# SERVOS.net
KiCad netlist of a schematic drawn in Altium Designer
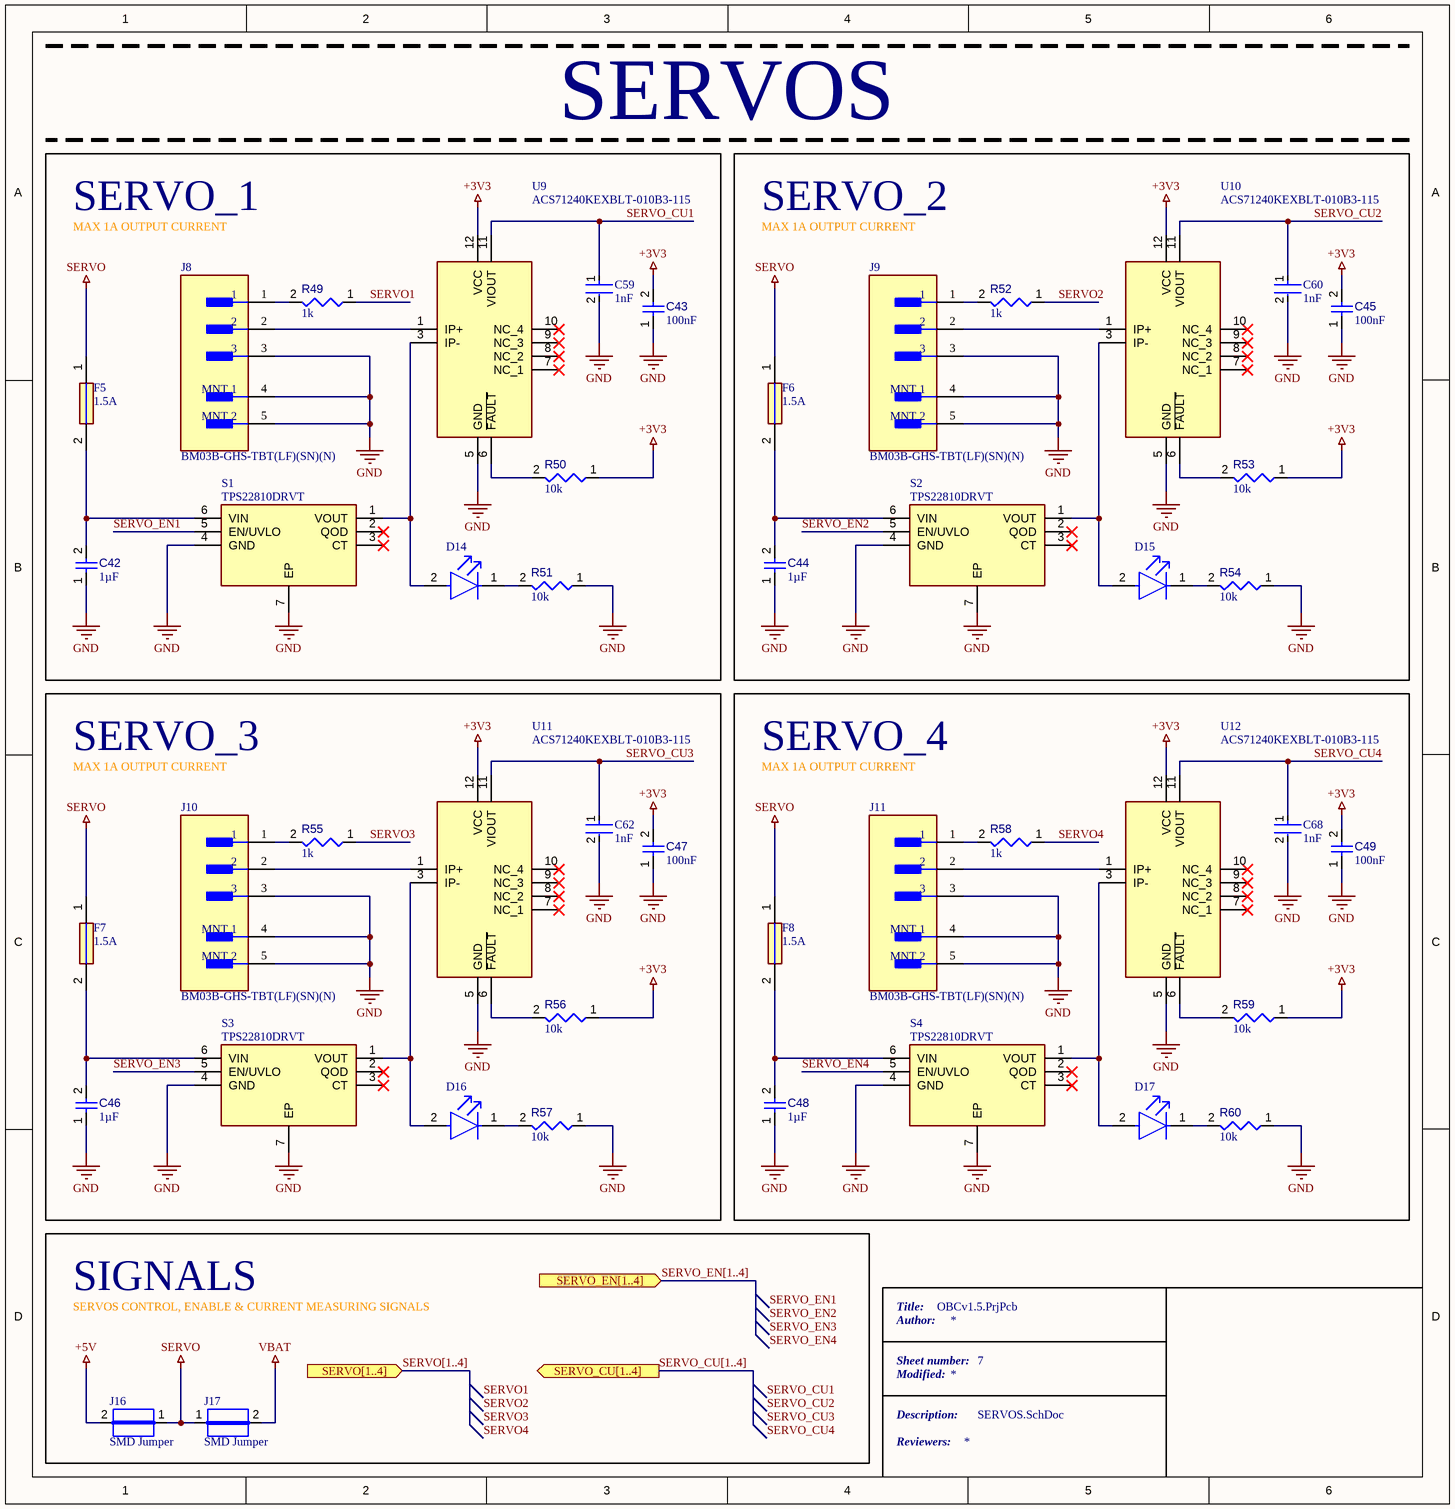
[diagram p0: SERVOS.SchDoc]

(export (version "E")
  (design (tool "Eeschema 10.0.6"))
  (components
    (comp (ref "C42")
      (value "1µF")
      (footprint "CAPC0402(1005)60_L")
      (description "Chip Capacitor, 1µF +/-20%, 10V, 0402, Thickness 0.6 mm")
      (fields (field (name "TOLERANCE") "10%") (field (name "Comment") "Capacitor 1µF +/-20% 10V 0402"))
      (libsource (lib "PWr in Space team") (part "CAP-NP-2"))
    )
    (comp (ref "C43")
      (value "100nF")
      (footprint "CAPC0402(1005)60_L")
      (description "Chip Capacitor, 100nF +/-20%, 10V, 0402, Thickness 0.6 mm")
      (fields (field (name "TOLERANCE") "20%") (field (name "Comment") "Capacitor 100nF +/-20% 10V 0402"))
      (libsource (lib "PWr in Space team") (part "CAP-NP-2"))
    )
    (comp (ref "C44")
      (value "1µF")
      (footprint "CAPC0402(1005)60_L")
      (description "Chip Capacitor, 1µF +/-20%, 10V, 0402, Thickness 0.6 mm")
      (fields (field (name "TOLERANCE") "10%") (field (name "Comment") "Capacitor 1µF +/-20% 10V 0402"))
      (libsource (lib "PWr in Space team") (part "CAP-NP-2"))
    )
    (comp (ref "C45")
      (value "100nF")
      (footprint "CAPC0402(1005)60_L")
      (description "Chip Capacitor, 100nF +/-20%, 10V, 0402, Thickness 0.6 mm")
      (fields (field (name "TOLERANCE") "20%") (field (name "Comment") "Capacitor 100nF +/-20% 10V 0402"))
      (libsource (lib "PWr in Space team") (part "CAP-NP-2"))
    )
    (comp (ref "C46")
      (value "1µF")
      (footprint "CAPC0402(1005)60_L")
      (description "Chip Capacitor, 1µF +/-20%, 10V, 0402, Thickness 0.6 mm")
      (fields (field (name "TOLERANCE") "10%") (field (name "Comment") "Capacitor 1µF +/-20% 10V 0402"))
      (libsource (lib "PWr in Space team") (part "CAP-NP-2"))
    )
    (comp (ref "C47")
      (value "100nF")
      (footprint "CAPC0402(1005)60_L")
      (description "Chip Capacitor, 100nF +/-20%, 10V, 0402, Thickness 0.6 mm")
      (fields (field (name "TOLERANCE") "20%") (field (name "Comment") "Capacitor 100nF +/-20% 10V 0402"))
      (libsource (lib "PWr in Space team") (part "CAP-NP-2"))
    )
    (comp (ref "C48")
      (value "1µF")
      (footprint "CAPC0402(1005)60_L")
      (description "Chip Capacitor, 1µF +/-20%, 10V, 0402, Thickness 0.6 mm")
      (fields (field (name "TOLERANCE") "10%") (field (name "Comment") "Capacitor 1µF +/-20% 10V 0402"))
      (libsource (lib "PWr in Space team") (part "CAP-NP-2"))
    )
    (comp (ref "C49")
      (value "100nF")
      (footprint "CAPC0402(1005)60_L")
      (description "Chip Capacitor, 100nF +/-20%, 10V, 0402, Thickness 0.6 mm")
      (fields (field (name "TOLERANCE") "20%") (field (name "Comment") "Capacitor 100nF +/-20% 10V 0402"))
      (libsource (lib "PWr in Space team") (part "CAP-NP-2"))
    )
    (comp (ref "C59")
      (value "1nF")
      (footprint "FP-GRM155-0_05-IPC_B")
      (description "Chip Multilayer Ceramic Capacitors for General Purpose, 0402, 1000pF, C0G, 30ppm/°C, 5%, 50V")
      (fields (field (name "TOLERANCE") "5%") (field (name "VOLTAGE") "50V"))
      (libsource (lib "Altium Content Vault") (part "02cd4be3c70576c341d710602a673aa"))
    )
    (comp (ref "C60")
      (value "1nF")
      (footprint "FP-GRM155-0_05-IPC_B")
      (description "Chip Multilayer Ceramic Capacitors for General Purpose, 0402, 1000pF, C0G, 30ppm/°C, 5%, 50V")
      (fields (field (name "TOLERANCE") "5%") (field (name "VOLTAGE") "50V"))
      (libsource (lib "Altium Content Vault") (part "02cd4be3c70576c341d710602a673aa"))
    )
    (comp (ref "C62")
      (value "1nF")
      (footprint "FP-GRM155-0_05-IPC_B")
      (description "Chip Multilayer Ceramic Capacitors for General Purpose, 0402, 1000pF, C0G, 30ppm/°C, 5%, 50V")
      (fields (field (name "TOLERANCE") "5%") (field (name "VOLTAGE") "50V"))
      (libsource (lib "Altium Content Vault") (part "02cd4be3c70576c341d710602a673aa"))
    )
    (comp (ref "C68")
      (value "1nF")
      (footprint "FP-GRM155-0_05-IPC_B")
      (description "Chip Multilayer Ceramic Capacitors for General Purpose, 0402, 1000pF, C0G, 30ppm/°C, 5%, 50V")
      (fields (field (name "TOLERANCE") "5%") (field (name "VOLTAGE") "50V"))
      (libsource (lib "Altium Content Vault") (part "02cd4be3c70576c341d710602a673aa"))
    )
    (comp (ref "D14")
      (value "~")
      (footprint "FP-LTST-C191TBKT-MFG")
      (description "LED BLUE CLEAR CHIP SMD")
      (libsource (lib "Altium Content Vault") (part "8706943c75ba83719d021d2fdc84c58"))
    )
    (comp (ref "D15")
      (value "~")
      (footprint "FP-LTST-C191TBKT-MFG")
      (description "LED BLUE CLEAR CHIP SMD")
      (libsource (lib "Altium Content Vault") (part "8706943c75ba83719d021d2fdc84c58"))
    )
    (comp (ref "D16")
      (value "~")
      (footprint "FP-LTST-C191TBKT-MFG")
      (description "LED BLUE CLEAR CHIP SMD")
      (libsource (lib "Altium Content Vault") (part "8706943c75ba83719d021d2fdc84c58"))
    )
    (comp (ref "D17")
      (value "~")
      (footprint "FP-LTST-C191TBKT-MFG")
      (description "LED BLUE CLEAR CHIP SMD")
      (libsource (lib "Altium Content Vault") (part "8706943c75ba83719d021d2fdc84c58"))
    )
    (comp (ref "F5")
      (value "1.5A")
      (footprint "SamacSys:FUSC2516X100N")
      (description "Fuse")
      (fields (field (name "MANUFACTURER_PART_NUMBER") "PTSLR08058V300"))
      (libsource (lib "*") (part "PTSLR08058V300"))
    )
    (comp (ref "F6")
      (value "1.5A")
      (footprint "SamacSys:FUSC2516X100N")
      (description "Fuse")
      (fields (field (name "MANUFACTURER_PART_NUMBER") "PTSLR08058V300"))
      (libsource (lib "*") (part "PTSLR08058V300"))
    )
    (comp (ref "F7")
      (value "1.5A")
      (footprint "SamacSys:FUSC2516X100N")
      (description "Fuse")
      (fields (field (name "MANUFACTURER_PART_NUMBER") "PTSLR08058V300"))
      (libsource (lib "*") (part "PTSLR08058V300"))
    )
    (comp (ref "F8")
      (value "1.5A")
      (footprint "SamacSys:FUSC2516X100N")
      (description "Fuse")
      (fields (field (name "MANUFACTURER_PART_NUMBER") "PTSLR08058V300"))
      (libsource (lib "*") (part "PTSLR08058V300"))
    )
    (comp (ref "J8")
      (value "BM03B-GHS-TBT(LF)(SN)(N)")
      (footprint "FP-BM03B-GHS-TBT_LF_SN-MFG")
      (description "CONN HEADER SMD 3POS 1.25MM")
      (libsource (lib "Altium Content Vault") (part "38689d6f3df0f9b234c6ddcef280d85"))
    )
    (comp (ref "J9")
      (value "BM03B-GHS-TBT(LF)(SN)(N)")
      (footprint "FP-BM03B-GHS-TBT_LF_SN-MFG")
      (description "CONN HEADER SMD 3POS 1.25MM")
      (libsource (lib "Altium Content Vault") (part "38689d6f3df0f9b234c6ddcef280d85"))
    )
    (comp (ref "J10")
      (value "BM03B-GHS-TBT(LF)(SN)(N)")
      (footprint "FP-BM03B-GHS-TBT_LF_SN-MFG")
      (description "CONN HEADER SMD 3POS 1.25MM")
      (libsource (lib "Altium Content Vault") (part "38689d6f3df0f9b234c6ddcef280d85"))
    )
    (comp (ref "J11")
      (value "BM03B-GHS-TBT(LF)(SN)(N)")
      (footprint "FP-BM03B-GHS-TBT_LF_SN-MFG")
      (description "CONN HEADER SMD 3POS 1.25MM")
      (libsource (lib "Altium Content Vault") (part "38689d6f3df0f9b234c6ddcef280d85"))
    )
    (comp (ref "J16")
      (value "SMD Jumper")
      (footprint "RESC3225X06N")
      (description "SMD Jumper, size 1210 (imperial)")
      (libsource (lib "PWr in Space team") (part "JUMPER"))
    )
    (comp (ref "J17")
      (value "SMD Jumper")
      (footprint "RESC3225X06N")
      (description "SMD Jumper, size 1210 (imperial)")
      (libsource (lib "") (part "JUMPER_1"))
    )
    (comp (ref "R49")
      (value "1k")
      (footprint "RESC0402(1005)_L")
      (description "Chip Resistor, 1 kOhms, +/-5 %, 63 mW, -55 to 155 degC, 0402")
      (fields (field (name "TOLERANCE") "5%") (field (name "POWER") "63mW"))
      (libsource (lib "PWr in Space team") (part "RES-2"))
    )
    (comp (ref "R50")
      (value "10k")
      (footprint "RESC0402(1005)_L")
      (description "Chip Resistor, 10 kOhms, +/-1 %, 63 mW, -55 to 125 degC, 0402")
      (fields (field (name "POWER") "63mW") (field (name "TOLERANCE") "1%"))
      (libsource (lib "PWr in Space team") (part "RES-2"))
    )
    (comp (ref "R51")
      (value "10k")
      (footprint "RESC0402(1005)_L")
      (description "Chip Resistor, 10 kOhms, +/-1 %, 63 mW, -55 to 125 degC, 0402")
      (fields (field (name "POWER") "63mW") (field (name "TOLERANCE") "1%"))
      (libsource (lib "PWr in Space team") (part "RES-2"))
    )
    (comp (ref "R52")
      (value "1k")
      (footprint "RESC0402(1005)_L")
      (description "Chip Resistor, 1 kOhms, +/-5 %, 63 mW, -55 to 155 degC, 0402")
      (fields (field (name "TOLERANCE") "5%") (field (name "POWER") "63mW"))
      (libsource (lib "PWr in Space team") (part "RES-2"))
    )
    (comp (ref "R53")
      (value "10k")
      (footprint "RESC0402(1005)_L")
      (description "Chip Resistor, 10 kOhms, +/-1 %, 63 mW, -55 to 125 degC, 0402")
      (fields (field (name "POWER") "63mW") (field (name "TOLERANCE") "1%"))
      (libsource (lib "PWr in Space team") (part "RES-2"))
    )
    (comp (ref "R54")
      (value "10k")
      (footprint "RESC0402(1005)_L")
      (description "Chip Resistor, 10 kOhms, +/-1 %, 63 mW, -55 to 125 degC, 0402")
      (fields (field (name "POWER") "63mW") (field (name "TOLERANCE") "1%"))
      (libsource (lib "PWr in Space team") (part "RES-2"))
    )
    (comp (ref "R55")
      (value "1k")
      (footprint "RESC0402(1005)_L")
      (description "Chip Resistor, 1 kOhms, +/-5 %, 63 mW, -55 to 155 degC, 0402")
      (fields (field (name "TOLERANCE") "5%") (field (name "POWER") "63mW"))
      (libsource (lib "PWr in Space team") (part "RES-2"))
    )
    (comp (ref "R56")
      (value "10k")
      (footprint "RESC0402(1005)_L")
      (description "Chip Resistor, 10 kOhms, +/-1 %, 63 mW, -55 to 125 degC, 0402")
      (fields (field (name "POWER") "63mW") (field (name "TOLERANCE") "1%"))
      (libsource (lib "PWr in Space team") (part "RES-2"))
    )
    (comp (ref "R57")
      (value "10k")
      (footprint "RESC0402(1005)_L")
      (description "Chip Resistor, 10 kOhms, +/-1 %, 63 mW, -55 to 125 degC, 0402")
      (fields (field (name "POWER") "63mW") (field (name "TOLERANCE") "1%"))
      (libsource (lib "PWr in Space team") (part "RES-2"))
    )
    (comp (ref "R58")
      (value "1k")
      (footprint "RESC0402(1005)_L")
      (description "Chip Resistor, 1 kOhms, +/-5 %, 63 mW, -55 to 155 degC, 0402")
      (fields (field (name "TOLERANCE") "5%") (field (name "POWER") "63mW"))
      (libsource (lib "PWr in Space team") (part "RES-2"))
    )
    (comp (ref "R59")
      (value "10k")
      (footprint "RESC0402(1005)_L")
      (description "Chip Resistor, 10 kOhms, +/-1 %, 63 mW, -55 to 125 degC, 0402")
      (fields (field (name "POWER") "63mW") (field (name "TOLERANCE") "1%"))
      (libsource (lib "PWr in Space team") (part "RES-2"))
    )
    (comp (ref "R60")
      (value "10k")
      (footprint "RESC0402(1005)_L")
      (description "Chip Resistor, 10 kOhms, +/-1 %, 63 mW, -55 to 125 degC, 0402")
      (fields (field (name "POWER") "63mW") (field (name "TOLERANCE") "1%"))
      (libsource (lib "PWr in Space team") (part "RES-2"))
    )
    (comp (ref "S1")
      (value "TPS22810DRVT")
      (footprint "SamacSys:SON65P200X200X80-7N")
      (description "Switch")
      (fields (field (name "MOUSER PART NUMBER") "595-TPS22810DRVT"))
      (libsource (lib "*") (part "TPS22810DRVT"))
    )
    (comp (ref "S2")
      (value "TPS22810DRVT")
      (footprint "SamacSys:SON65P200X200X80-7N")
      (description "Switch")
      (fields (field (name "MOUSER PART NUMBER") "595-TPS22810DRVT"))
      (libsource (lib "*") (part "TPS22810DRVT"))
    )
    (comp (ref "S3")
      (value "TPS22810DRVT")
      (footprint "SamacSys:SON65P200X200X80-7N")
      (description "Switch")
      (fields (field (name "MOUSER PART NUMBER") "595-TPS22810DRVT"))
      (libsource (lib "*") (part "TPS22810DRVT"))
    )
    (comp (ref "S4")
      (value "TPS22810DRVT")
      (footprint "SamacSys:SON65P200X200X80-7N")
      (description "Switch")
      (fields (field (name "MOUSER PART NUMBER") "595-TPS22810DRVT"))
      (libsource (lib "*") (part "TPS22810DRVT"))
    )
    (comp (ref "U9")
      (value "ACS71240KEXBLT-010B3-115")
      (footprint "SamacSys:ACS71240KEXBLT010B3115")
      (description "Integrated Circuit")
      (fields (field (name "MOUSER PART NUMBER") "250-71240KEXBL0B3115"))
      (libsource (lib "*") (part "ACS71240KEXBLT-010B3-115"))
    )
    (comp (ref "U10")
      (value "ACS71240KEXBLT-010B3-115")
      (footprint "SamacSys:ACS71240KEXBLT010B3115")
      (description "Integrated Circuit")
      (fields (field (name "MOUSER PART NUMBER") "250-71240KEXBL0B3115"))
      (libsource (lib "*") (part "ACS71240KEXBLT-010B3-115"))
    )
    (comp (ref "U11")
      (value "ACS71240KEXBLT-010B3-115")
      (footprint "SamacSys:ACS71240KEXBLT010B3115")
      (description "Integrated Circuit")
      (fields (field (name "MOUSER PART NUMBER") "250-71240KEXBL0B3115"))
      (libsource (lib "*") (part "ACS71240KEXBLT-010B3-115"))
    )
    (comp (ref "U12")
      (value "ACS71240KEXBLT-010B3-115")
      (footprint "SamacSys:ACS71240KEXBLT010B3115")
      (description "Integrated Circuit")
      (fields (field (name "MOUSER PART NUMBER") "250-71240KEXBL0B3115"))
      (libsource (lib "*") (part "ACS71240KEXBLT-010B3-115"))
    )
  )
  (nets
    (net (code "1") (name "+3V3") (class "Default")
      (node (ref "C43") (pin "2") (pinfunction "2_2") (pintype "passive"))
      (node (ref "C45") (pin "2") (pinfunction "2_2") (pintype "passive"))
      (node (ref "C47") (pin "2") (pinfunction "2_2") (pintype "passive"))
      (node (ref "C49") (pin "2") (pinfunction "2_2") (pintype "passive"))
      (node (ref "R50") (pin "1") (pinfunction "1_1") (pintype "passive"))
      (node (ref "R53") (pin "1") (pinfunction "1_1") (pintype "passive"))
      (node (ref "R56") (pin "1") (pinfunction "1_1") (pintype "passive"))
      (node (ref "R59") (pin "1") (pinfunction "1_1") (pintype "passive"))
      (node (ref "U10") (pin "12") (pinfunction "VCC_12") (pintype "passive"))
      (node (ref "U11") (pin "12") (pinfunction "VCC_12") (pintype "passive"))
      (node (ref "U12") (pin "12") (pinfunction "VCC_12") (pintype "passive"))
      (node (ref "U9") (pin "12") (pinfunction "VCC_12") (pintype "passive"))
    )
    (net (code "2") (name "+5V") (class "Default")
      (node (ref "J16") (pin "2") (pinfunction "2_2") (pintype "passive"))
    )
    (net (code "3") (name "/SERVO1") (class "Default")
      (node (ref "R49") (pin "1") (pinfunction "1_1") (pintype "passive"))
    )
    (net (code "4") (name "/SERVO2") (class "Default")
      (node (ref "R52") (pin "1") (pinfunction "1_1") (pintype "passive"))
    )
    (net (code "5") (name "/SERVO3") (class "Default")
      (node (ref "R55") (pin "1") (pinfunction "1_1") (pintype "passive"))
    )
    (net (code "6") (name "/SERVO4") (class "Default")
      (node (ref "R58") (pin "1") (pinfunction "1_1") (pintype "passive"))
    )
    (net (code "8") (name "/SERVO_CU1") (class "Default")
      (node (ref "C59") (pin "1") (pinfunction "1_1") (pintype "passive"))
      (node (ref "U9") (pin "11") (pinfunction "VIOUT_11") (pintype "passive"))
    )
    (net (code "9") (name "/SERVO_CU2") (class "Default")
      (node (ref "C60") (pin "1") (pinfunction "1_1") (pintype "passive"))
      (node (ref "U10") (pin "11") (pinfunction "VIOUT_11") (pintype "passive"))
    )
    (net (code "10") (name "/SERVO_CU3") (class "Default")
      (node (ref "C62") (pin "1") (pinfunction "1_1") (pintype "passive"))
      (node (ref "U11") (pin "11") (pinfunction "VIOUT_11") (pintype "passive"))
    )
    (net (code "11") (name "/SERVO_CU4") (class "Default")
      (node (ref "C68") (pin "1") (pinfunction "1_1") (pintype "passive"))
      (node (ref "U12") (pin "11") (pinfunction "VIOUT_11") (pintype "passive"))
    )
    (net (code "13") (name "/SERVO_EN1") (class "Default")
      (node (ref "S1") (pin "5") (pinfunction "EN/UVLO_5") (pintype "passive"))
    )
    (net (code "14") (name "/SERVO_EN2") (class "Default")
      (node (ref "S2") (pin "5") (pinfunction "EN/UVLO_5") (pintype "passive"))
    )
    (net (code "15") (name "/SERVO_EN3") (class "Default")
      (node (ref "S3") (pin "5") (pinfunction "EN/UVLO_5") (pintype "passive"))
    )
    (net (code "16") (name "/SERVO_EN4") (class "Default")
      (node (ref "S4") (pin "5") (pinfunction "EN/UVLO_5") (pintype "passive"))
    )
    (net (code "18") (name "GND") (class "Default")
      (node (ref "C42") (pin "1") (pinfunction "1_1") (pintype "passive"))
      (node (ref "C43") (pin "1") (pinfunction "1_1") (pintype "passive"))
      (node (ref "C44") (pin "1") (pinfunction "1_1") (pintype "passive"))
      (node (ref "C45") (pin "1") (pinfunction "1_1") (pintype "passive"))
      (node (ref "C46") (pin "1") (pinfunction "1_1") (pintype "passive"))
      (node (ref "C47") (pin "1") (pinfunction "1_1") (pintype "passive"))
      (node (ref "C48") (pin "1") (pinfunction "1_1") (pintype "passive"))
      (node (ref "C49") (pin "1") (pinfunction "1_1") (pintype "passive"))
      (node (ref "C59") (pin "2") (pinfunction "2_2") (pintype "passive"))
      (node (ref "C60") (pin "2") (pinfunction "2_2") (pintype "passive"))
      (node (ref "C62") (pin "2") (pinfunction "2_2") (pintype "passive"))
      (node (ref "C68") (pin "2") (pinfunction "2_2") (pintype "passive"))
      (node (ref "J10") (pin "3") (pinfunction "3_3") (pintype "passive"))
      (node (ref "J10") (pin "4") (pinfunction "MNT_1_4") (pintype "passive"))
      (node (ref "J10") (pin "5") (pinfunction "MNT_2_5") (pintype "passive"))
      (node (ref "J11") (pin "3") (pinfunction "3_3") (pintype "passive"))
      (node (ref "J11") (pin "4") (pinfunction "MNT_1_4") (pintype "passive"))
      (node (ref "J11") (pin "5") (pinfunction "MNT_2_5") (pintype "passive"))
      (node (ref "J8") (pin "3") (pinfunction "3_3") (pintype "passive"))
      (node (ref "J8") (pin "4") (pinfunction "MNT_1_4") (pintype "passive"))
      (node (ref "J8") (pin "5") (pinfunction "MNT_2_5") (pintype "passive"))
      (node (ref "J9") (pin "3") (pinfunction "3_3") (pintype "passive"))
      (node (ref "J9") (pin "4") (pinfunction "MNT_1_4") (pintype "passive"))
      (node (ref "J9") (pin "5") (pinfunction "MNT_2_5") (pintype "passive"))
      (node (ref "R51") (pin "1") (pinfunction "1_1") (pintype "passive"))
      (node (ref "R54") (pin "1") (pinfunction "1_1") (pintype "passive"))
      (node (ref "R57") (pin "1") (pinfunction "1_1") (pintype "passive"))
      (node (ref "R60") (pin "1") (pinfunction "1_1") (pintype "passive"))
      (node (ref "S1") (pin "4") (pinfunction "GND_4") (pintype "passive"))
      (node (ref "S1") (pin "7") (pinfunction "EP_7") (pintype "passive"))
      (node (ref "S2") (pin "4") (pinfunction "GND_4") (pintype "passive"))
      (node (ref "S2") (pin "7") (pinfunction "EP_7") (pintype "passive"))
      (node (ref "S3") (pin "4") (pinfunction "GND_4") (pintype "passive"))
      (node (ref "S3") (pin "7") (pinfunction "EP_7") (pintype "passive"))
      (node (ref "S4") (pin "4") (pinfunction "GND_4") (pintype "passive"))
      (node (ref "S4") (pin "7") (pinfunction "EP_7") (pintype "passive"))
      (node (ref "U10") (pin "5") (pinfunction "GND_5") (pintype "passive"))
      (node (ref "U11") (pin "5") (pinfunction "GND_5") (pintype "passive"))
      (node (ref "U12") (pin "5") (pinfunction "GND_5") (pintype "passive"))
      (node (ref "U9") (pin "5") (pinfunction "GND_5") (pintype "passive"))
    )
    (net (code "19") (name "Net-(D14-A)") (class "Default")
      (node (ref "D14") (pin "2") (pinfunction "A_2") (pintype "passive"))
      (node (ref "S1") (pin "1") (pinfunction "VOUT_1") (pintype "passive"))
      (node (ref "U9") (pin "3") (pinfunction "IP-_3") (pintype "passive"))
    )
    (net (code "20") (name "Net-(D14-C)") (class "Default")
      (node (ref "D14") (pin "1") (pinfunction "C_1") (pintype "passive"))
      (node (ref "R51") (pin "2") (pinfunction "2_2") (pintype "passive"))
    )
    (net (code "21") (name "Net-(D15-A)") (class "Default")
      (node (ref "D15") (pin "2") (pinfunction "A_2") (pintype "passive"))
      (node (ref "S2") (pin "1") (pinfunction "VOUT_1") (pintype "passive"))
      (node (ref "U10") (pin "3") (pinfunction "IP-_3") (pintype "passive"))
    )
    (net (code "22") (name "Net-(D15-C)") (class "Default")
      (node (ref "D15") (pin "1") (pinfunction "C_1") (pintype "passive"))
      (node (ref "R54") (pin "2") (pinfunction "2_2") (pintype "passive"))
    )
    (net (code "23") (name "Net-(D16-A)") (class "Default")
      (node (ref "D16") (pin "2") (pinfunction "A_2") (pintype "passive"))
      (node (ref "S3") (pin "1") (pinfunction "VOUT_1") (pintype "passive"))
      (node (ref "U11") (pin "3") (pinfunction "IP-_3") (pintype "passive"))
    )
    (net (code "24") (name "Net-(D16-C)") (class "Default")
      (node (ref "D16") (pin "1") (pinfunction "C_1") (pintype "passive"))
      (node (ref "R57") (pin "2") (pinfunction "2_2") (pintype "passive"))
    )
    (net (code "25") (name "Net-(D17-A)") (class "Default")
      (node (ref "D17") (pin "2") (pinfunction "A_2") (pintype "passive"))
      (node (ref "S4") (pin "1") (pinfunction "VOUT_1") (pintype "passive"))
      (node (ref "U12") (pin "3") (pinfunction "IP-_3") (pintype "passive"))
    )
    (net (code "26") (name "Net-(D17-C)") (class "Default")
      (node (ref "D17") (pin "1") (pinfunction "C_1") (pintype "passive"))
      (node (ref "R60") (pin "2") (pinfunction "2_2") (pintype "passive"))
    )
    (net (code "27") (name "Net-(J8-Pad1)") (class "Default")
      (node (ref "J8") (pin "1") (pinfunction "1_1") (pintype "passive"))
      (node (ref "R49") (pin "2") (pinfunction "2_2") (pintype "passive"))
    )
    (net (code "28") (name "Net-(J9-Pad1)") (class "Default")
      (node (ref "J9") (pin "1") (pinfunction "1_1") (pintype "passive"))
      (node (ref "R52") (pin "2") (pinfunction "2_2") (pintype "passive"))
    )
    (net (code "29") (name "Net-(J10-Pad1)") (class "Default")
      (node (ref "J10") (pin "1") (pinfunction "1_1") (pintype "passive"))
      (node (ref "R55") (pin "2") (pinfunction "2_2") (pintype "passive"))
    )
    (net (code "30") (name "Net-(J11-Pad1)") (class "Default")
      (node (ref "J11") (pin "1") (pinfunction "1_1") (pintype "passive"))
      (node (ref "R58") (pin "2") (pinfunction "2_2") (pintype "passive"))
    )
    (net (code "31") (name "Net-(S1-VIN)") (class "Default")
      (node (ref "C42") (pin "2") (pinfunction "2_2") (pintype "passive"))
      (node (ref "F5") (pin "2") (pinfunction "2_2") (pintype "passive"))
      (node (ref "S1") (pin "6") (pinfunction "VIN_6") (pintype "passive"))
    )
    (net (code "32") (name "Net-(S2-VIN)") (class "Default")
      (node (ref "C44") (pin "2") (pinfunction "2_2") (pintype "passive"))
      (node (ref "F6") (pin "2") (pinfunction "2_2") (pintype "passive"))
      (node (ref "S2") (pin "6") (pinfunction "VIN_6") (pintype "passive"))
    )
    (net (code "33") (name "Net-(S3-VIN)") (class "Default")
      (node (ref "C46") (pin "2") (pinfunction "2_2") (pintype "passive"))
      (node (ref "F7") (pin "2") (pinfunction "2_2") (pintype "passive"))
      (node (ref "S3") (pin "6") (pinfunction "VIN_6") (pintype "passive"))
    )
    (net (code "34") (name "Net-(S4-VIN)") (class "Default")
      (node (ref "C48") (pin "2") (pinfunction "2_2") (pintype "passive"))
      (node (ref "F8") (pin "2") (pinfunction "2_2") (pintype "passive"))
      (node (ref "S4") (pin "6") (pinfunction "VIN_6") (pintype "passive"))
    )
    (net (code "35") (name "Net-(U9-IP+)") (class "Default")
      (node (ref "J8") (pin "2") (pinfunction "2_2") (pintype "passive"))
      (node (ref "U9") (pin "1") (pinfunction "IP+_1") (pintype "passive"))
    )
    (net (code "36") (name "Net-(U9-~{FAULT})") (class "Default")
      (node (ref "R50") (pin "2") (pinfunction "2_2") (pintype "passive"))
      (node (ref "U9") (pin "6") (pinfunction "~{FAULT}_6") (pintype "passive"))
    )
    (net (code "37") (name "Net-(U10-IP+)") (class "Default")
      (node (ref "J9") (pin "2") (pinfunction "2_2") (pintype "passive"))
      (node (ref "U10") (pin "1") (pinfunction "IP+_1") (pintype "passive"))
    )
    (net (code "38") (name "Net-(U10-~{FAULT})") (class "Default")
      (node (ref "R53") (pin "2") (pinfunction "2_2") (pintype "passive"))
      (node (ref "U10") (pin "6") (pinfunction "~{FAULT}_6") (pintype "passive"))
    )
    (net (code "39") (name "Net-(U11-IP+)") (class "Default")
      (node (ref "J10") (pin "2") (pinfunction "2_2") (pintype "passive"))
      (node (ref "U11") (pin "1") (pinfunction "IP+_1") (pintype "passive"))
    )
    (net (code "40") (name "Net-(U11-~{FAULT})") (class "Default")
      (node (ref "R56") (pin "2") (pinfunction "2_2") (pintype "passive"))
      (node (ref "U11") (pin "6") (pinfunction "~{FAULT}_6") (pintype "passive"))
    )
    (net (code "41") (name "Net-(U12-IP+)") (class "Default")
      (node (ref "J11") (pin "2") (pinfunction "2_2") (pintype "passive"))
      (node (ref "U12") (pin "1") (pinfunction "IP+_1") (pintype "passive"))
    )
    (net (code "42") (name "Net-(U12-~{FAULT})") (class "Default")
      (node (ref "R59") (pin "2") (pinfunction "2_2") (pintype "passive"))
      (node (ref "U12") (pin "6") (pinfunction "~{FAULT}_6") (pintype "passive"))
    )
    (net (code "43") (name "SERVO") (class "Default")
      (node (ref "F5") (pin "1") (pinfunction "1_1") (pintype "passive"))
      (node (ref "F6") (pin "1") (pinfunction "1_1") (pintype "passive"))
      (node (ref "F7") (pin "1") (pinfunction "1_1") (pintype "passive"))
      (node (ref "F8") (pin "1") (pinfunction "1_1") (pintype "passive"))
      (node (ref "J16") (pin "1") (pinfunction "1_1") (pintype "passive"))
      (node (ref "J17") (pin "1") (pinfunction "1_1") (pintype "passive"))
    )
    (net (code "44") (name "VBAT") (class "Default")
      (node (ref "J17") (pin "2") (pinfunction "2_2") (pintype "passive"))
    )
    (net (code "45") (name "unconnected-(S1-CT-Pad3)") (class "Default")
      (node (ref "S1") (pin "3") (pinfunction "CT_3") (pintype "passive+no_connect"))
    )
    (net (code "46") (name "unconnected-(S1-QOD-Pad2)") (class "Default")
      (node (ref "S1") (pin "2") (pinfunction "QOD_2") (pintype "passive+no_connect"))
    )
    (net (code "47") (name "unconnected-(S2-CT-Pad3)") (class "Default")
      (node (ref "S2") (pin "3") (pinfunction "CT_3") (pintype "passive+no_connect"))
    )
    (net (code "48") (name "unconnected-(S2-QOD-Pad2)") (class "Default")
      (node (ref "S2") (pin "2") (pinfunction "QOD_2") (pintype "passive+no_connect"))
    )
    (net (code "49") (name "unconnected-(S3-CT-Pad3)") (class "Default")
      (node (ref "S3") (pin "3") (pinfunction "CT_3") (pintype "passive+no_connect"))
    )
    (net (code "50") (name "unconnected-(S3-QOD-Pad2)") (class "Default")
      (node (ref "S3") (pin "2") (pinfunction "QOD_2") (pintype "passive+no_connect"))
    )
    (net (code "51") (name "unconnected-(S4-CT-Pad3)") (class "Default")
      (node (ref "S4") (pin "3") (pinfunction "CT_3") (pintype "passive+no_connect"))
    )
    (net (code "52") (name "unconnected-(S4-QOD-Pad2)") (class "Default")
      (node (ref "S4") (pin "2") (pinfunction "QOD_2") (pintype "passive+no_connect"))
    )
    (net (code "53") (name "unconnected-(U9-NC_1-Pad7)") (class "Default")
      (node (ref "U9") (pin "7") (pinfunction "NC_1_7") (pintype "passive+no_connect"))
    )
    (net (code "54") (name "unconnected-(U9-NC_2-Pad8)") (class "Default")
      (node (ref "U9") (pin "8") (pinfunction "NC_2_8") (pintype "passive+no_connect"))
    )
    (net (code "55") (name "unconnected-(U9-NC_3-Pad9)") (class "Default")
      (node (ref "U9") (pin "9") (pinfunction "NC_3_9") (pintype "passive+no_connect"))
    )
    (net (code "56") (name "unconnected-(U9-NC_4-Pad10)") (class "Default")
      (node (ref "U9") (pin "10") (pinfunction "NC_4_10") (pintype "passive+no_connect"))
    )
    (net (code "57") (name "unconnected-(U10-NC_1-Pad7)") (class "Default")
      (node (ref "U10") (pin "7") (pinfunction "NC_1_7") (pintype "passive+no_connect"))
    )
    (net (code "58") (name "unconnected-(U10-NC_2-Pad8)") (class "Default")
      (node (ref "U10") (pin "8") (pinfunction "NC_2_8") (pintype "passive+no_connect"))
    )
    (net (code "59") (name "unconnected-(U10-NC_3-Pad9)") (class "Default")
      (node (ref "U10") (pin "9") (pinfunction "NC_3_9") (pintype "passive+no_connect"))
    )
    (net (code "60") (name "unconnected-(U10-NC_4-Pad10)") (class "Default")
      (node (ref "U10") (pin "10") (pinfunction "NC_4_10") (pintype "passive+no_connect"))
    )
    (net (code "61") (name "unconnected-(U11-NC_1-Pad7)") (class "Default")
      (node (ref "U11") (pin "7") (pinfunction "NC_1_7") (pintype "passive+no_connect"))
    )
    (net (code "62") (name "unconnected-(U11-NC_2-Pad8)") (class "Default")
      (node (ref "U11") (pin "8") (pinfunction "NC_2_8") (pintype "passive+no_connect"))
    )
    (net (code "63") (name "unconnected-(U11-NC_3-Pad9)") (class "Default")
      (node (ref "U11") (pin "9") (pinfunction "NC_3_9") (pintype "passive+no_connect"))
    )
    (net (code "64") (name "unconnected-(U11-NC_4-Pad10)") (class "Default")
      (node (ref "U11") (pin "10") (pinfunction "NC_4_10") (pintype "passive+no_connect"))
    )
    (net (code "65") (name "unconnected-(U12-NC_1-Pad7)") (class "Default")
      (node (ref "U12") (pin "7") (pinfunction "NC_1_7") (pintype "passive+no_connect"))
    )
    (net (code "66") (name "unconnected-(U12-NC_2-Pad8)") (class "Default")
      (node (ref "U12") (pin "8") (pinfunction "NC_2_8") (pintype "passive+no_connect"))
    )
    (net (code "67") (name "unconnected-(U12-NC_3-Pad9)") (class "Default")
      (node (ref "U12") (pin "9") (pinfunction "NC_3_9") (pintype "passive+no_connect"))
    )
    (net (code "68") (name "unconnected-(U12-NC_4-Pad10)") (class "Default")
      (node (ref "U12") (pin "10") (pinfunction "NC_4_10") (pintype "passive+no_connect"))
    )
  )
)
